# DRAM_POD_1.net
KiCad netlist of a schematic drawn in EAGLE
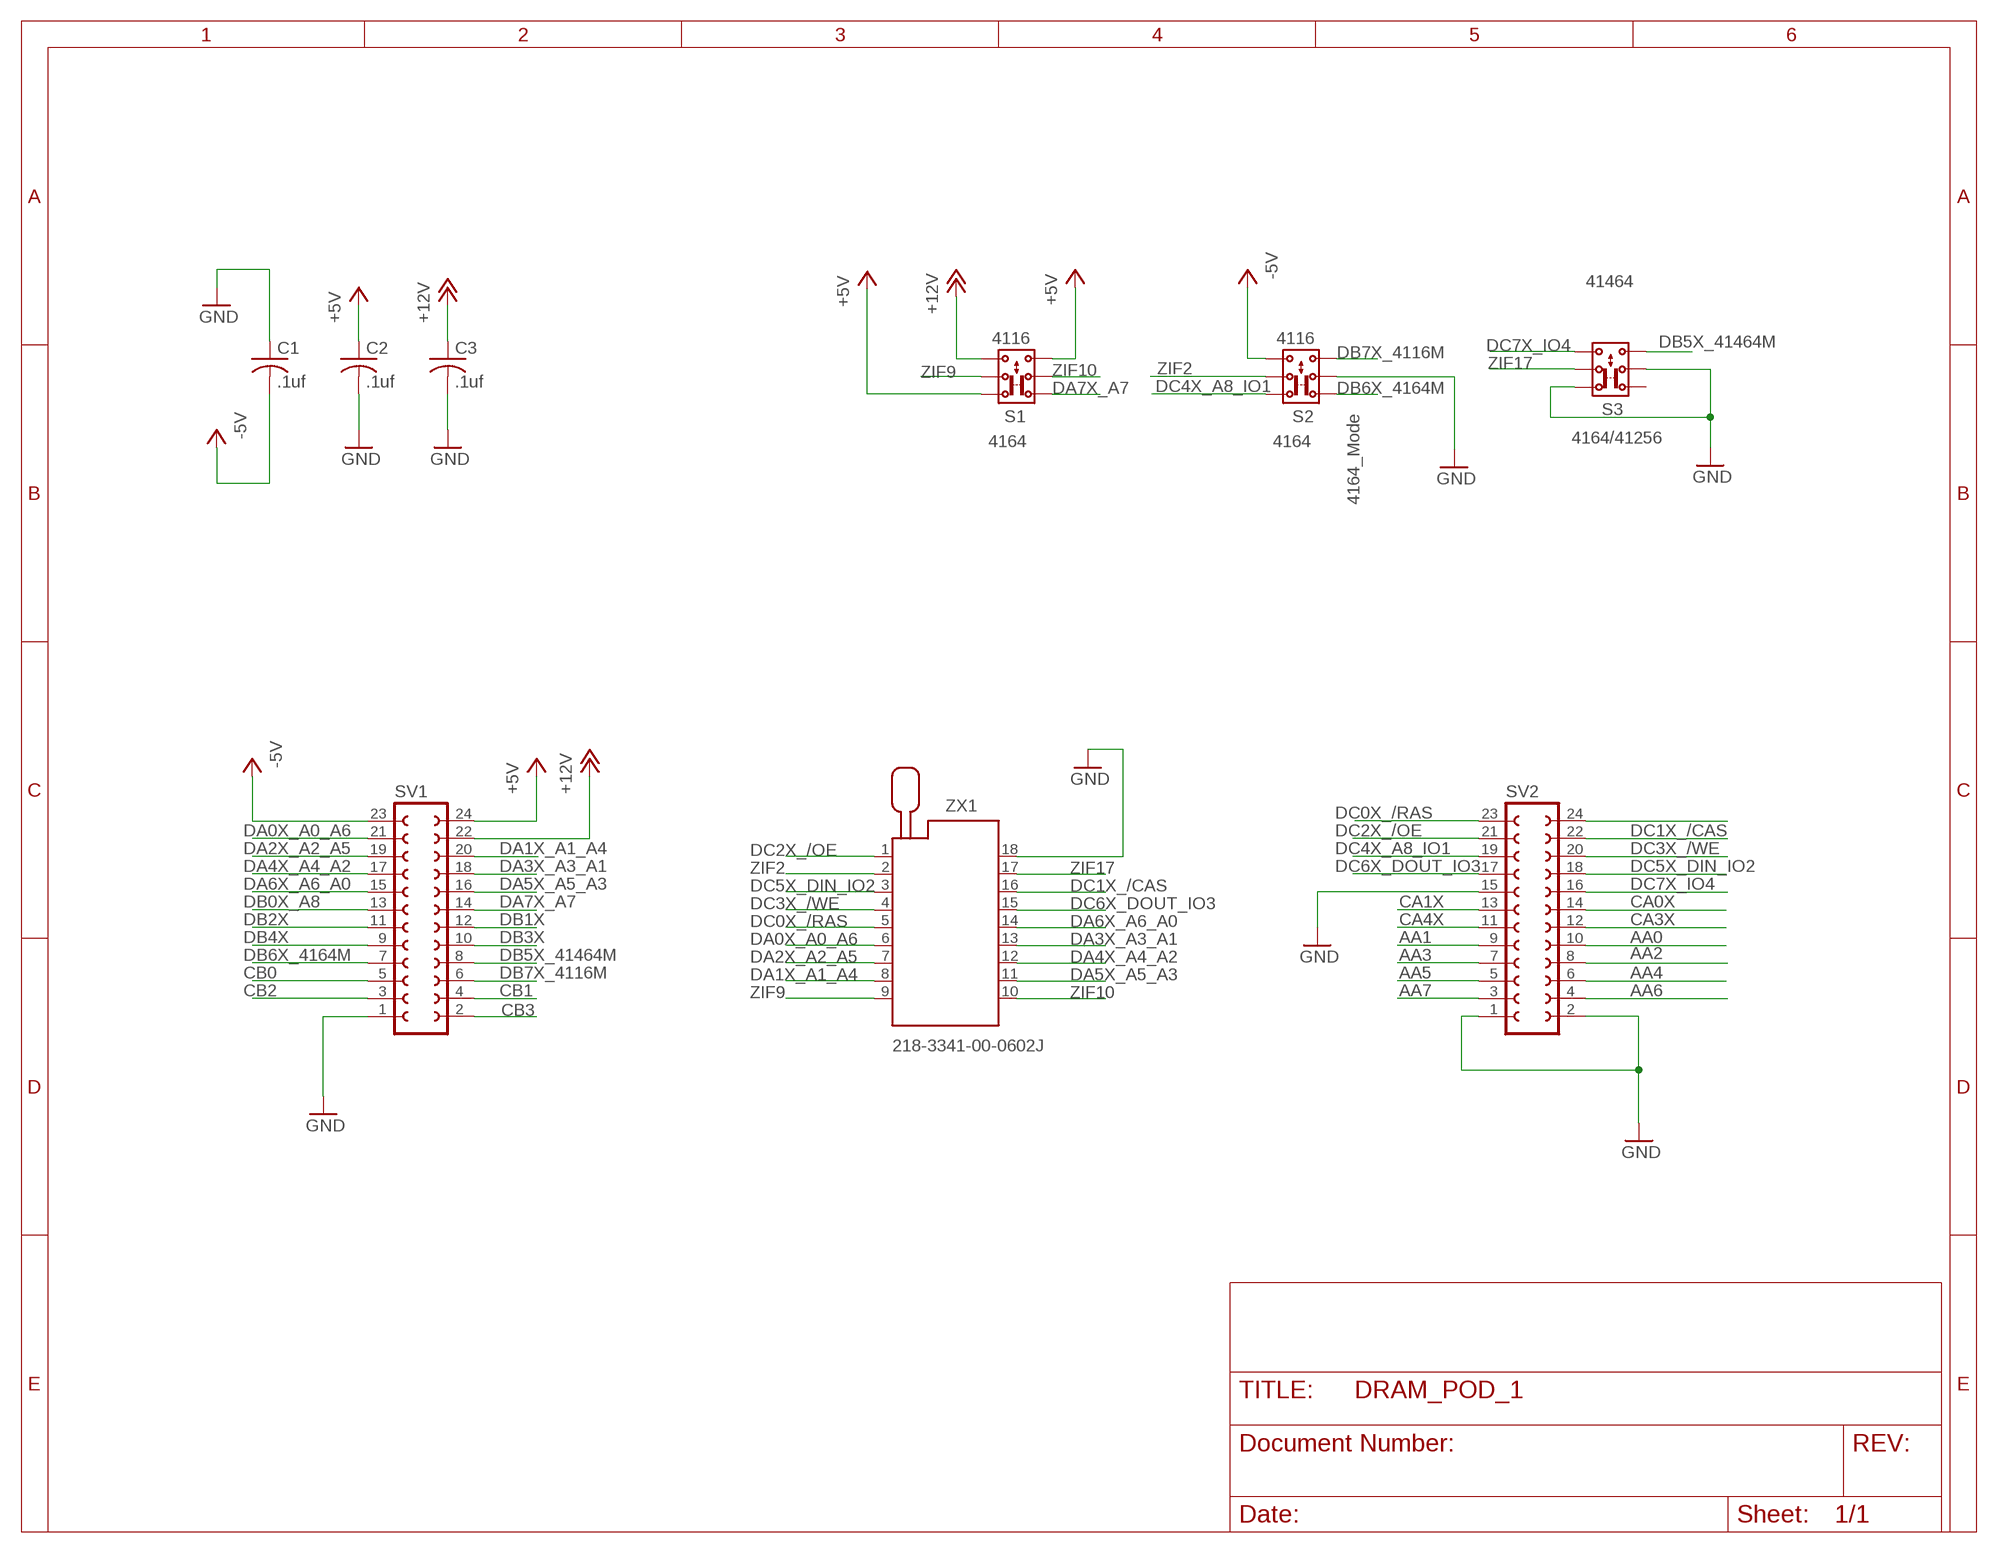
[diagram p0: schematic, sheet 1]

(export (version "E")
  (design (tool "Eeschema 10.0.6"))
  (components
    (comp (ref "C1")
      (value ".1uf")
      (footprint "eagle-import:C025-024X044")
      (libsource (lib "eagle-import") (part "C-US025-024X044"))
    )
    (comp (ref "C2")
      (value ".1uf")
      (footprint "eagle-import:C025-024X044")
      (libsource (lib "eagle-import") (part "C-US025-024X044"))
    )
    (comp (ref "C3")
      (value ".1uf")
      (footprint "eagle-import:C025-024X044")
      (libsource (lib "eagle-import") (part "C-US025-024X044"))
    )
    (comp (ref "S1")
      (value "2P2T")
      (footprint "eagle-import:2P2T")
      (libsource (lib "eagle-import") (part "2P2T"))
    )
    (comp (ref "S2")
      (value "2P2T")
      (footprint "eagle-import:2P2T")
      (libsource (lib "eagle-import") (part "2P2T"))
    )
    (comp (ref "S3")
      (value "2P2T")
      (footprint "eagle-import:2P2T")
      (libsource (lib "eagle-import") (part "2P2T"))
    )
    (comp (ref "SV1")
      (value "FE12-2")
      (footprint "eagle-import:FE12-2")
      (libsource (lib "eagle-import") (part "FE12-2"))
    )
    (comp (ref "SV2")
      (value "FE12-2")
      (footprint "eagle-import:FE12-2")
      (libsource (lib "eagle-import") (part "FE12-2"))
    )
    (comp (ref "ZX1")
      (value "218-3341-00-0602J")
      (footprint "eagle-import:218-3341-00-0602J")
      (fields (field (name "MF") "3M"))
      (libsource (lib "eagle-import") (part "218-3341-00-0602J"))
    )
  )
  (nets
    (net (code "1") (name "+5V") (class "Default")
      (node (ref "C2") (pin "1") (pinfunction "1_1") (pintype "passive"))
      (node (ref "S1") (pin "1.1") (pinfunction "1.1_1.1") (pintype "passive"))
      (node (ref "S1") (pin "3.2") (pinfunction "3.2_3.2") (pintype "passive"))
      (node (ref "SV1") (pin "24") (pinfunction "24_24") (pintype "passive"))
    )
    (net (code "2") (name "+12V") (class "Default")
      (node (ref "C3") (pin "1") (pinfunction "1_1") (pintype "passive"))
      (node (ref "S1") (pin "3.1") (pinfunction "3.1_3.1") (pintype "passive"))
      (node (ref "SV1") (pin "22") (pinfunction "22_22") (pintype "passive"))
    )
    (net (code "3") (name "-5V") (class "Default")
      (node (ref "C1") (pin "2") (pinfunction "2_2") (pintype "passive"))
      (node (ref "S2") (pin "3.1") (pinfunction "3.1_3.1") (pintype "passive"))
      (node (ref "SV1") (pin "23") (pinfunction "23_23") (pintype "passive"))
    )
    (net (code "4") (name "/AA0") (class "Default")
      (node (ref "SV2") (pin "10") (pinfunction "10_10") (pintype "passive"))
    )
    (net (code "5") (name "/AA1") (class "Default")
      (node (ref "SV2") (pin "9") (pinfunction "9_9") (pintype "passive"))
    )
    (net (code "6") (name "/AA2") (class "Default")
      (node (ref "SV2") (pin "8") (pinfunction "8_8") (pintype "passive"))
    )
    (net (code "7") (name "/AA3") (class "Default")
      (node (ref "SV2") (pin "7") (pinfunction "7_7") (pintype "passive"))
    )
    (net (code "8") (name "/AA4") (class "Default")
      (node (ref "SV2") (pin "6") (pinfunction "6_6") (pintype "passive"))
    )
    (net (code "9") (name "/AA5") (class "Default")
      (node (ref "SV2") (pin "5") (pinfunction "5_5") (pintype "passive"))
    )
    (net (code "10") (name "/AA6") (class "Default")
      (node (ref "SV2") (pin "4") (pinfunction "4_4") (pintype "passive"))
    )
    (net (code "11") (name "/AA7") (class "Default")
      (node (ref "SV2") (pin "3") (pinfunction "3_3") (pintype "passive"))
    )
    (net (code "12") (name "/CA0X") (class "Default")
      (node (ref "SV2") (pin "14") (pinfunction "14_14") (pintype "passive"))
    )
    (net (code "13") (name "/CA1X") (class "Default")
      (node (ref "SV2") (pin "13") (pinfunction "13_13") (pintype "passive"))
    )
    (net (code "14") (name "/CA3X") (class "Default")
      (node (ref "SV2") (pin "12") (pinfunction "12_12") (pintype "passive"))
    )
    (net (code "15") (name "/CA4X") (class "Default")
      (node (ref "SV2") (pin "11") (pinfunction "11_11") (pintype "passive"))
    )
    (net (code "16") (name "/CB0") (class "Default")
      (node (ref "SV1") (pin "5") (pinfunction "5_5") (pintype "passive"))
    )
    (net (code "17") (name "/CB1") (class "Default")
      (node (ref "SV1") (pin "4") (pinfunction "4_4") (pintype "passive"))
    )
    (net (code "18") (name "/CB2") (class "Default")
      (node (ref "SV1") (pin "3") (pinfunction "3_3") (pintype "passive"))
    )
    (net (code "19") (name "/CB3") (class "Default")
      (node (ref "SV1") (pin "2") (pinfunction "2_2") (pintype "passive"))
    )
    (net (code "20") (name "/DA0X_A0_A6") (class "Default")
      (node (ref "SV1") (pin "21") (pinfunction "21_21") (pintype "passive"))
      (node (ref "ZX1") (pin "6") (pinfunction "6_6") (pintype "passive"))
    )
    (net (code "21") (name "/DA1X_A1_A4") (class "Default")
      (node (ref "SV1") (pin "20") (pinfunction "20_20") (pintype "passive"))
      (node (ref "ZX1") (pin "8") (pinfunction "8_8") (pintype "passive"))
    )
    (net (code "22") (name "/DA2X_A2_A5") (class "Default")
      (node (ref "SV1") (pin "19") (pinfunction "19_19") (pintype "passive"))
      (node (ref "ZX1") (pin "7") (pinfunction "7_7") (pintype "passive"))
    )
    (net (code "23") (name "/DA3X_A3_A1") (class "Default")
      (node (ref "SV1") (pin "18") (pinfunction "18_18") (pintype "passive"))
      (node (ref "ZX1") (pin "13") (pinfunction "13_13") (pintype "passive"))
    )
    (net (code "24") (name "/DA4X_A4_A2") (class "Default")
      (node (ref "SV1") (pin "17") (pinfunction "17_17") (pintype "passive"))
      (node (ref "ZX1") (pin "12") (pinfunction "12_12") (pintype "passive"))
    )
    (net (code "25") (name "/DA5X_A5_A3") (class "Default")
      (node (ref "SV1") (pin "16") (pinfunction "16_16") (pintype "passive"))
      (node (ref "ZX1") (pin "11") (pinfunction "11_11") (pintype "passive"))
    )
    (net (code "26") (name "/DA6X_A6_A0") (class "Default")
      (node (ref "SV1") (pin "15") (pinfunction "15_15") (pintype "passive"))
      (node (ref "ZX1") (pin "14") (pinfunction "14_14") (pintype "passive"))
    )
    (net (code "27") (name "/DA7X_A7") (class "Default")
      (node (ref "S1") (pin "1.2") (pinfunction "1.2_1.2") (pintype "passive"))
      (node (ref "SV1") (pin "14") (pinfunction "14_14") (pintype "passive"))
    )
    (net (code "28") (name "/DB0X_A8") (class "Default")
      (node (ref "SV1") (pin "13") (pinfunction "13_13") (pintype "passive"))
    )
    (net (code "29") (name "/DB1X") (class "Default")
      (node (ref "SV1") (pin "12") (pinfunction "12_12") (pintype "passive"))
    )
    (net (code "30") (name "/DB2X") (class "Default")
      (node (ref "SV1") (pin "11") (pinfunction "11_11") (pintype "passive"))
    )
    (net (code "31") (name "/DB3X") (class "Default")
      (node (ref "SV1") (pin "10") (pinfunction "10_10") (pintype "passive"))
    )
    (net (code "32") (name "/DB4X") (class "Default")
      (node (ref "SV1") (pin "9") (pinfunction "9_9") (pintype "passive"))
    )
    (net (code "33") (name "/DB5X_41464M") (class "Default")
      (node (ref "S3") (pin "3.2") (pinfunction "3.2_3.2") (pintype "passive"))
      (node (ref "SV1") (pin "8") (pinfunction "8_8") (pintype "passive"))
    )
    (net (code "34") (name "/DB6X_4164M") (class "Default")
      (node (ref "S2") (pin "1.2") (pinfunction "1.2_1.2") (pintype "passive"))
      (node (ref "SV1") (pin "7") (pinfunction "7_7") (pintype "passive"))
    )
    (net (code "35") (name "/DB7X_4116M") (class "Default")
      (node (ref "S2") (pin "3.2") (pinfunction "3.2_3.2") (pintype "passive"))
      (node (ref "SV1") (pin "6") (pinfunction "6_6") (pintype "passive"))
    )
    (net (code "36") (name "/DC0X_{slash}RAS") (class "Default")
      (node (ref "SV2") (pin "23") (pinfunction "23_23") (pintype "passive"))
      (node (ref "ZX1") (pin "5") (pinfunction "5_5") (pintype "passive"))
    )
    (net (code "37") (name "/DC1X_{slash}CAS") (class "Default")
      (node (ref "SV2") (pin "22") (pinfunction "22_22") (pintype "passive"))
      (node (ref "ZX1") (pin "16") (pinfunction "16_16") (pintype "passive"))
    )
    (net (code "38") (name "/DC2X_{slash}OE") (class "Default")
      (node (ref "SV2") (pin "21") (pinfunction "21_21") (pintype "passive"))
      (node (ref "ZX1") (pin "1") (pinfunction "1_1") (pintype "passive"))
    )
    (net (code "39") (name "/DC3X_{slash}WE") (class "Default")
      (node (ref "SV2") (pin "20") (pinfunction "20_20") (pintype "passive"))
      (node (ref "ZX1") (pin "4") (pinfunction "4_4") (pintype "passive"))
    )
    (net (code "40") (name "/DC4X_A8_IO1") (class "Default")
      (node (ref "S2") (pin "1.1") (pinfunction "1.1_1.1") (pintype "passive"))
      (node (ref "SV2") (pin "19") (pinfunction "19_19") (pintype "passive"))
    )
    (net (code "41") (name "/DC5X_DIN_IO2") (class "Default")
      (node (ref "SV2") (pin "18") (pinfunction "18_18") (pintype "passive"))
      (node (ref "ZX1") (pin "3") (pinfunction "3_3") (pintype "passive"))
    )
    (net (code "42") (name "/DC6X_DOUT_IO3") (class "Default")
      (node (ref "SV2") (pin "17") (pinfunction "17_17") (pintype "passive"))
      (node (ref "ZX1") (pin "15") (pinfunction "15_15") (pintype "passive"))
    )
    (net (code "43") (name "/DC7X_IO4") (class "Default")
      (node (ref "S3") (pin "3.1") (pinfunction "3.1_3.1") (pintype "passive"))
      (node (ref "SV2") (pin "16") (pinfunction "16_16") (pintype "passive"))
    )
    (net (code "44") (name "/ZIF2") (class "Default")
      (node (ref "S2") (pin "2.1") (pinfunction "2.1_2.1") (pintype "passive"))
      (node (ref "ZX1") (pin "2") (pinfunction "2_2") (pintype "passive"))
    )
    (net (code "45") (name "/ZIF9") (class "Default")
      (node (ref "S1") (pin "2.1") (pinfunction "2.1_2.1") (pintype "passive"))
      (node (ref "ZX1") (pin "9") (pinfunction "9_9") (pintype "passive"))
    )
    (net (code "46") (name "/ZIF10") (class "Default")
      (node (ref "S1") (pin "2.2") (pinfunction "2.2_2.2") (pintype "passive"))
      (node (ref "ZX1") (pin "10") (pinfunction "10_10") (pintype "passive"))
    )
    (net (code "47") (name "/ZIF17") (class "Default")
      (node (ref "S3") (pin "2.1") (pinfunction "2.1_2.1") (pintype "passive"))
      (node (ref "ZX1") (pin "17") (pinfunction "17_17") (pintype "passive"))
    )
    (net (code "48") (name "GND") (class "Default")
      (node (ref "C1") (pin "1") (pinfunction "1_1") (pintype "passive"))
      (node (ref "C2") (pin "2") (pinfunction "2_2") (pintype "passive"))
      (node (ref "C3") (pin "2") (pinfunction "2_2") (pintype "passive"))
      (node (ref "S2") (pin "2.2") (pinfunction "2.2_2.2") (pintype "passive"))
      (node (ref "S3") (pin "1.1") (pinfunction "1.1_1.1") (pintype "passive"))
      (node (ref "S3") (pin "2.2") (pinfunction "2.2_2.2") (pintype "passive"))
      (node (ref "SV1") (pin "1") (pinfunction "1_1") (pintype "passive"))
      (node (ref "SV2") (pin "1") (pinfunction "1_1") (pintype "passive"))
      (node (ref "SV2") (pin "15") (pinfunction "15_15") (pintype "passive"))
      (node (ref "SV2") (pin "2") (pinfunction "2_2") (pintype "passive"))
      (node (ref "ZX1") (pin "18") (pinfunction "18_18") (pintype "passive"))
    )
    (net (code "49") (name "unconnected-(S3-Pad1.2)") (class "Default")
      (node (ref "S3") (pin "1.2") (pinfunction "1.2_1.2") (pintype "passive"))
    )
    (net (code "50") (name "unconnected-(SV2-Pad24)") (class "Default")
      (node (ref "SV2") (pin "24") (pinfunction "24_24") (pintype "passive"))
    )
  )
)
